# sw-4416-project-v1.net
KiCad netlist of a schematic drawn in EAGLE
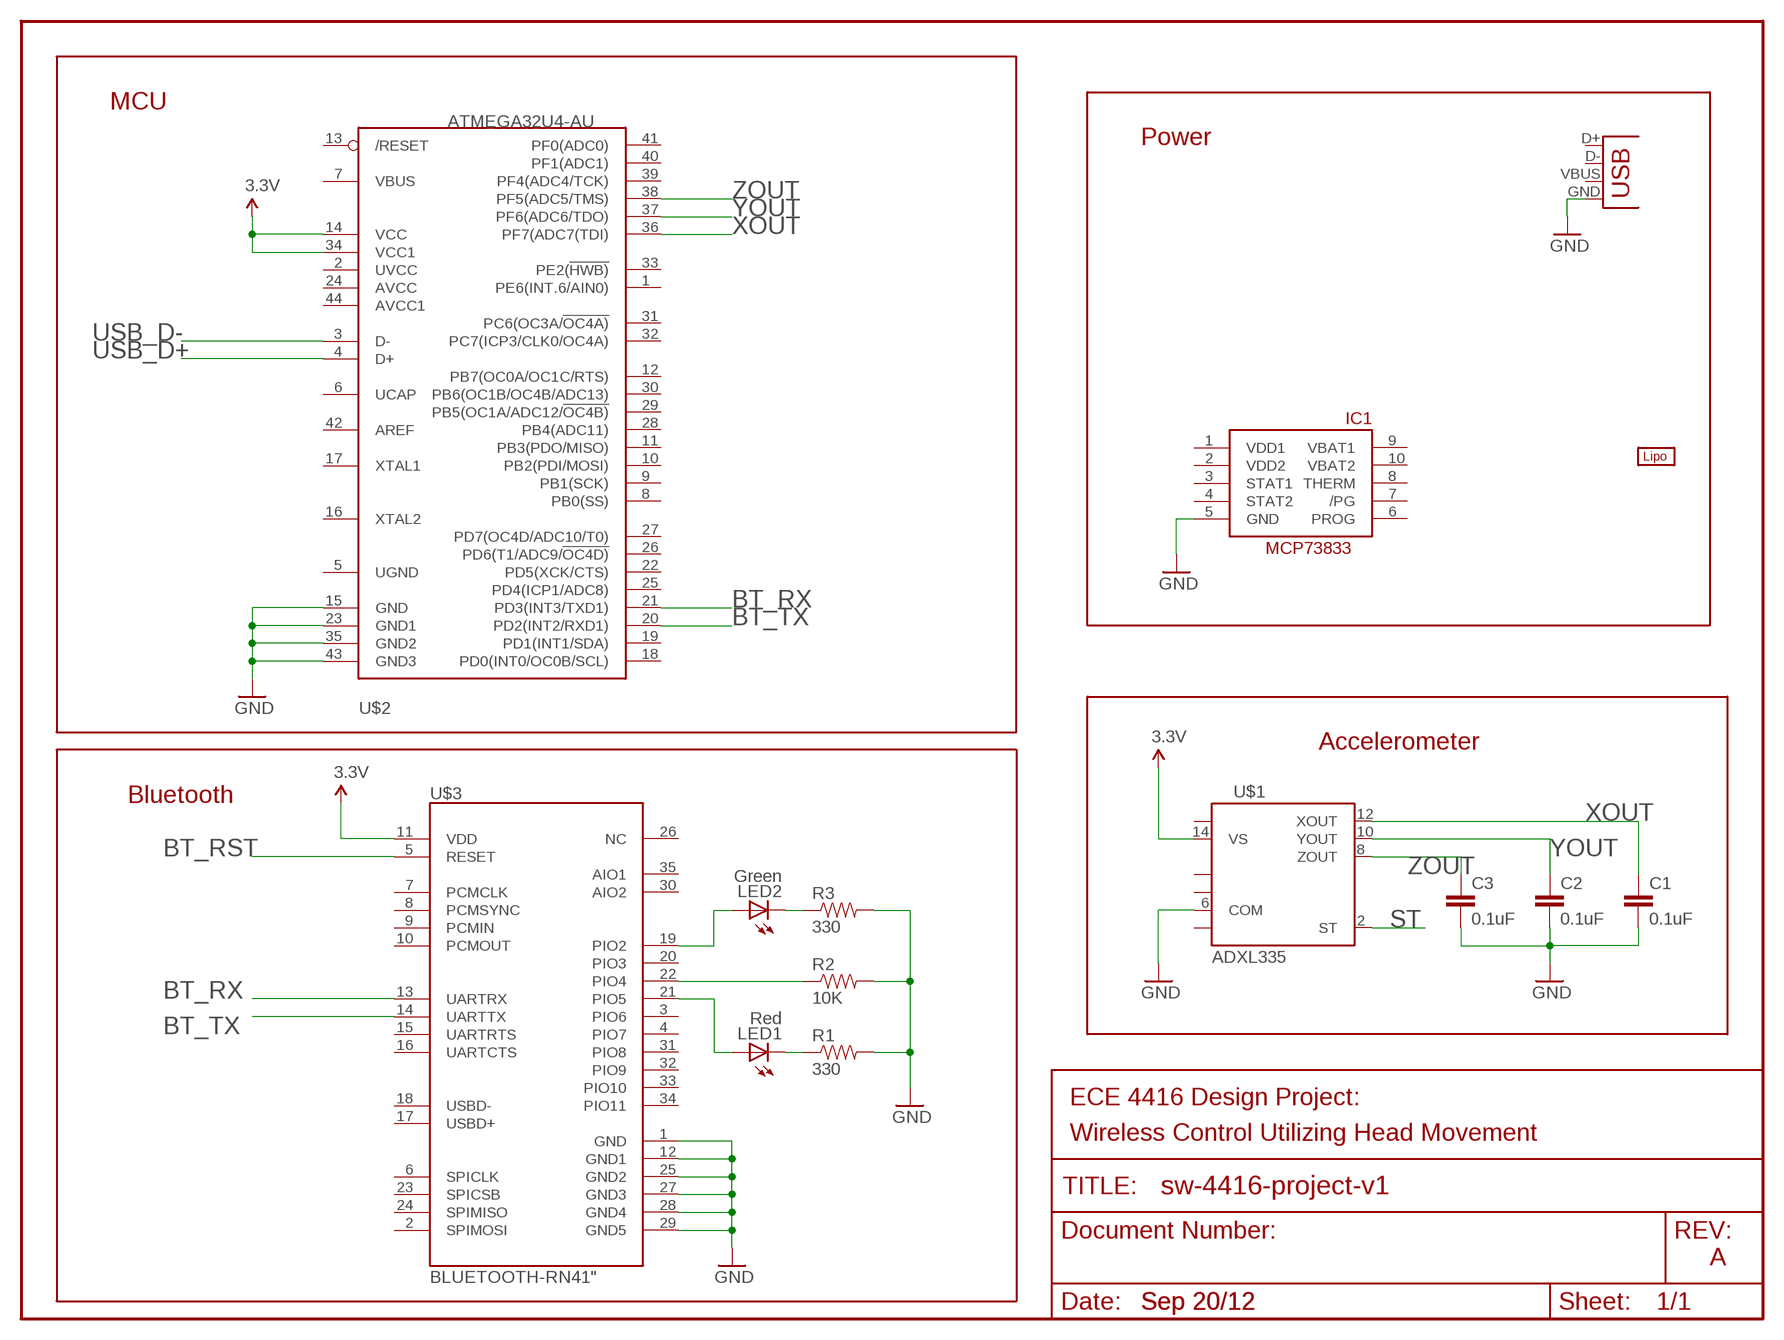
[diagram p0: schematic, sheet 1]

(export (version "E")
  (design (tool "Eeschema 10.0.6"))
  (components
    (comp (ref "C1")
      (value "0.1uF")
      (footprint "eagle-import:0603-CAP")
      (libsource (lib "eagle-import") (part "CAP0603-CAP"))
    )
    (comp (ref "C2")
      (value "0.1uF")
      (footprint "eagle-import:0603-CAP")
      (libsource (lib "eagle-import") (part "CAP0603-CAP"))
    )
    (comp (ref "C3")
      (value "0.1uF")
      (footprint "eagle-import:0603-CAP")
      (libsource (lib "eagle-import") (part "CAP0603-CAP"))
    )
    (comp (ref "IC1")
      (value "MCP73833-UN")
      (footprint "eagle-import:MSOP10")
      (libsource (lib "eagle-import") (part "MCP73833-UN"))
    )
    (comp (ref "LED1")
      (value "Red")
      (footprint "eagle-import:LED-0603")
      (libsource (lib "eagle-import") (part "LED0603"))
    )
    (comp (ref "LED2")
      (value "Green")
      (footprint "eagle-import:LED-0603")
      (libsource (lib "eagle-import") (part "LED0603"))
    )
    (comp (ref "R1")
      (value "330")
      (footprint "eagle-import:0603-RES")
      (libsource (lib "eagle-import") (part "RESISTOR0603-RES"))
    )
    (comp (ref "R2")
      (value "10K")
      (footprint "eagle-import:0603-RES")
      (libsource (lib "eagle-import") (part "RESISTOR0603-RES"))
    )
    (comp (ref "R3")
      (value "330")
      (footprint "eagle-import:0603-RES")
      (libsource (lib "eagle-import") (part "RESISTOR0603-RES"))
    )
    (comp (ref "U$1")
      (value "ADXL335")
      (footprint "eagle-import:LFCSP-16")
      (libsource (lib "eagle-import") (part "ADXL335"))
    )
    (comp (ref "U$2")
      (value "ATMEGA32U4-AU")
      (footprint "eagle-import:TQFP44")
      (libsource (lib "eagle-import") (part "ATMEGA32U4-AU"))
    )
    (comp (ref "U$3")
      (value "BLUETOOTH-RN41\"")
      (footprint "eagle-import:RN41")
      (libsource (lib "eagle-import") (part "BLUETOOTH-RN41{dblquote}"))
    )
    (comp (ref "U$4")
      (value "LIPO-OUTLINE1100")
      (footprint "eagle-import:LIPO-1100")
      (libsource (lib "eagle-import") (part "LIPO-OUTLINE1100"))
    )
    (comp (ref "X1")
      (value "USB-MICROB")
      (footprint "eagle-import:USB-MICROB")
      (libsource (lib "eagle-import") (part "USB-MICROB"))
    )
  )
  (nets
    (net (code "1") (name "/BT_RST") (class "Default")
      (node (ref "U$3") (pin "5") (pinfunction "RESET_5") (pintype "bidirectional"))
    )
    (net (code "2") (name "/BT_RX") (class "Default")
      (node (ref "U$2") (pin "21") (pinfunction "PD3(INT3/TXD1)_21") (pintype "bidirectional"))
      (node (ref "U$3") (pin "13") (pinfunction "UARTRX_13") (pintype "bidirectional"))
    )
    (net (code "3") (name "/BT_TX") (class "Default")
      (node (ref "U$2") (pin "20") (pinfunction "PD2(INT2/RXD1)_20") (pintype "bidirectional"))
      (node (ref "U$3") (pin "14") (pinfunction "UARTTX_14") (pintype "bidirectional"))
    )
    (net (code "4") (name "/ST") (class "Default")
      (node (ref "U$1") (pin "2") (pinfunction "ST_2") (pintype "bidirectional"))
    )
    (net (code "5") (name "/USB_D+") (class "Default")
      (node (ref "U$2") (pin "4") (pinfunction "D+_4") (pintype "bidirectional"))
    )
    (net (code "6") (name "/USB_D-") (class "Default")
      (node (ref "U$2") (pin "3") (pinfunction "D-_3") (pintype "bidirectional"))
    )
    (net (code "7") (name "/VDD1") (class "Default")
      (node (ref "IC1") (pin "1") (pinfunction "VDD1_1") (pintype "power_in"))
    )
    (net (code "8") (name "/VDD2") (class "Default")
      (node (ref "IC1") (pin "2") (pinfunction "VDD2_2") (pintype "power_in"))
    )
    (net (code "9") (name "/XOUT") (class "Default")
      (node (ref "C1") (pin "1") (pinfunction "1_1") (pintype "passive"))
      (node (ref "U$1") (pin "12") (pinfunction "XOUT_12") (pintype "bidirectional"))
      (node (ref "U$2") (pin "36") (pinfunction "PF7(ADC7(TDI)_36") (pintype "bidirectional"))
    )
    (net (code "10") (name "/YOUT") (class "Default")
      (node (ref "C2") (pin "1") (pinfunction "1_1") (pintype "passive"))
      (node (ref "U$1") (pin "10") (pinfunction "YOUT_10") (pintype "bidirectional"))
      (node (ref "U$2") (pin "37") (pinfunction "PF6(ADC6/TDO)_37") (pintype "bidirectional"))
    )
    (net (code "11") (name "/ZOUT") (class "Default")
      (node (ref "C3") (pin "1") (pinfunction "1_1") (pintype "passive"))
      (node (ref "U$1") (pin "8") (pinfunction "ZOUT_8") (pintype "bidirectional"))
      (node (ref "U$2") (pin "38") (pinfunction "PF5(ADC5/TMS)_38") (pintype "bidirectional"))
    )
    (net (code "12") (name "3.3V") (class "Default")
      (node (ref "U$1") (pin "14") (pinfunction "VS_14") (pintype "bidirectional"))
      (node (ref "U$2") (pin "14") (pinfunction "VCC_14") (pintype "bidirectional"))
      (node (ref "U$2") (pin "34") (pinfunction "VCC1_34") (pintype "bidirectional"))
      (node (ref "U$3") (pin "11") (pinfunction "VDD_11") (pintype "bidirectional"))
    )
    (net (code "13") (name "GND") (class "Default")
      (node (ref "C1") (pin "2") (pinfunction "2_2") (pintype "passive"))
      (node (ref "C2") (pin "2") (pinfunction "2_2") (pintype "passive"))
      (node (ref "C3") (pin "2") (pinfunction "2_2") (pintype "passive"))
      (node (ref "IC1") (pin "5") (pinfunction "GND_5") (pintype "power_in"))
      (node (ref "R1") (pin "2") (pinfunction "2_2") (pintype "passive"))
      (node (ref "R2") (pin "2") (pinfunction "2_2") (pintype "passive"))
      (node (ref "R3") (pin "2") (pinfunction "2_2") (pintype "passive"))
      (node (ref "U$1") (pin "6") (pinfunction "COM_6") (pintype "bidirectional"))
      (node (ref "U$2") (pin "15") (pinfunction "GND_15") (pintype "bidirectional"))
      (node (ref "U$2") (pin "23") (pinfunction "GND1_23") (pintype "bidirectional"))
      (node (ref "U$2") (pin "35") (pinfunction "GND2_35") (pintype "bidirectional"))
      (node (ref "U$2") (pin "43") (pinfunction "GND3_43") (pintype "bidirectional"))
      (node (ref "U$3") (pin "1") (pinfunction "GND_1") (pintype "bidirectional"))
      (node (ref "U$3") (pin "12") (pinfunction "GND1_12") (pintype "bidirectional"))
      (node (ref "U$3") (pin "25") (pinfunction "GND2_25") (pintype "bidirectional"))
      (node (ref "U$3") (pin "27") (pinfunction "GND3_27") (pintype "bidirectional"))
      (node (ref "U$3") (pin "28") (pinfunction "GND4_28") (pintype "bidirectional"))
      (node (ref "U$3") (pin "29") (pinfunction "GND5_29") (pintype "bidirectional"))
      (node (ref "X1") (pin "GND") (pinfunction "GND_GND") (pintype "bidirectional"))
    )
    (net (code "14") (name "Net-(LED1-PadC)") (class "Default")
      (node (ref "LED1") (pin "C") (pinfunction "C_C") (pintype "passive"))
      (node (ref "R1") (pin "1") (pinfunction "1_1") (pintype "passive"))
    )
    (net (code "15") (name "Net-(LED2-PadC)") (class "Default")
      (node (ref "LED2") (pin "C") (pinfunction "C_C") (pintype "passive"))
      (node (ref "R3") (pin "1") (pinfunction "1_1") (pintype "passive"))
    )
    (net (code "16") (name "Net-(U$3-PIO2)") (class "Default")
      (node (ref "LED2") (pin "A") (pinfunction "A_A") (pintype "passive"))
      (node (ref "U$3") (pin "19") (pinfunction "PIO2_19") (pintype "bidirectional"))
    )
    (net (code "17") (name "Net-(U$3-PIO4)") (class "Default")
      (node (ref "R2") (pin "1") (pinfunction "1_1") (pintype "passive"))
      (node (ref "U$3") (pin "22") (pinfunction "PIO4_22") (pintype "bidirectional"))
    )
    (net (code "18") (name "Net-(U$3-PIO5)") (class "Default")
      (node (ref "LED1") (pin "A") (pinfunction "A_A") (pintype "passive"))
      (node (ref "U$3") (pin "21") (pinfunction "PIO5_21") (pintype "bidirectional"))
    )
    (net (code "19") (name "unconnected-(IC1-PROG-Pad6)") (class "Default")
      (node (ref "IC1") (pin "6") (pinfunction "PROG_6") (pintype "input"))
    )
    (net (code "20") (name "unconnected-(IC1-STAT1-Pad3)") (class "Default")
      (node (ref "IC1") (pin "3") (pinfunction "STAT1_3") (pintype "passive"))
    )
    (net (code "21") (name "unconnected-(IC1-STAT2-Pad4)") (class "Default")
      (node (ref "IC1") (pin "4") (pinfunction "STAT2_4") (pintype "passive"))
    )
    (net (code "22") (name "unconnected-(IC1-THERM-Pad8)") (class "Default")
      (node (ref "IC1") (pin "8") (pinfunction "THERM_8") (pintype "bidirectional"))
    )
    (net (code "23") (name "unconnected-(IC1-VBAT1-Pad9)") (class "Default")
      (node (ref "IC1") (pin "9") (pinfunction "VBAT1_9") (pintype "output"))
    )
    (net (code "24") (name "unconnected-(IC1-VBAT2-Pad10)") (class "Default")
      (node (ref "IC1") (pin "10") (pinfunction "VBAT2_10") (pintype "output"))
    )
    (net (code "25") (name "unconnected-(IC1-{slash}PG-Pad7)") (class "Default")
      (node (ref "IC1") (pin "7") (pinfunction "/PG_7") (pintype "passive"))
    )
    (net (code "26") (name "unconnected-(U$1-COM-Pad3)") (class "Default")
      (node (ref "U$1") (pin "3") (pinfunction "COM_3") (pintype "bidirectional"))
    )
    (net (code "27") (name "unconnected-(U$1-COM-Pad5)") (class "Default")
      (node (ref "U$1") (pin "5") (pinfunction "COM_5") (pintype "bidirectional"))
    )
    (net (code "28") (name "unconnected-(U$1-COM-Pad7)") (class "Default")
      (node (ref "U$1") (pin "7") (pinfunction "COM_7") (pintype "bidirectional"))
    )
    (net (code "29") (name "unconnected-(U$1-VS-Pad15)") (class "Default")
      (node (ref "U$1") (pin "15") (pinfunction "VS_15") (pintype "bidirectional"))
    )
    (net (code "30") (name "unconnected-(U$2-AREF-Pad42)") (class "Default")
      (node (ref "U$2") (pin "42") (pinfunction "AREF_42") (pintype "bidirectional"))
    )
    (net (code "31") (name "unconnected-(U$2-AVCC-Pad24)") (class "Default")
      (node (ref "U$2") (pin "24") (pinfunction "AVCC_24") (pintype "bidirectional"))
    )
    (net (code "32") (name "unconnected-(U$2-AVCC1-Pad44)") (class "Default")
      (node (ref "U$2") (pin "44") (pinfunction "AVCC1_44") (pintype "bidirectional"))
    )
    (net (code "33") (name "unconnected-(U$2-PB0(SS)-Pad8)") (class "Default")
      (node (ref "U$2") (pin "8") (pinfunction "PB0(SS)_8") (pintype "bidirectional"))
    )
    (net (code "34") (name "unconnected-(U$2-PB1(SCK)-Pad9)") (class "Default")
      (node (ref "U$2") (pin "9") (pinfunction "PB1(SCK)_9") (pintype "bidirectional"))
    )
    (net (code "35") (name "unconnected-(U$2-PB2(PDI{slash}MOSI)-Pad10)") (class "Default")
      (node (ref "U$2") (pin "10") (pinfunction "PB2(PDI/MOSI)_10") (pintype "bidirectional"))
    )
    (net (code "36") (name "unconnected-(U$2-PB3(PDO{slash}MISO)-Pad11)") (class "Default")
      (node (ref "U$2") (pin "11") (pinfunction "PB3(PDO/MISO)_11") (pintype "bidirectional"))
    )
    (net (code "37") (name "unconnected-(U$2-PB4(ADC11)-Pad28)") (class "Default")
      (node (ref "U$2") (pin "28") (pinfunction "PB4(ADC11)_28") (pintype "bidirectional"))
    )
    (net (code "38") (name "unconnected-(U$2-PB5(OC1A{slash}ADC12{slash}~{OC4B})-Pad29)") (class "Default")
      (node (ref "U$2") (pin "29") (pinfunction "PB5(OC1A/ADC12/~{OC4B})_29") (pintype "bidirectional"))
    )
    (net (code "39") (name "unconnected-(U$2-PB6(OC1B{slash}OC4B{slash}ADC13)-Pad30)") (class "Default")
      (node (ref "U$2") (pin "30") (pinfunction "PB6(OC1B/OC4B/ADC13)_30") (pintype "bidirectional"))
    )
    (net (code "40") (name "unconnected-(U$2-PB7(OC0A{slash}OC1C{slash}RTS)-Pad12)") (class "Default")
      (node (ref "U$2") (pin "12") (pinfunction "PB7(OC0A/OC1C/RTS)_12") (pintype "bidirectional"))
    )
    (net (code "41") (name "unconnected-(U$2-PC6(OC3A{slash}~{OC4A})-Pad31)") (class "Default")
      (node (ref "U$2") (pin "31") (pinfunction "PC6(OC3A/~{OC4A})_31") (pintype "bidirectional"))
    )
    (net (code "42") (name "unconnected-(U$2-PC7(ICP3{slash}CLK0{slash}OC4A)-Pad32)") (class "Default")
      (node (ref "U$2") (pin "32") (pinfunction "PC7(ICP3/CLK0/OC4A)_32") (pintype "bidirectional"))
    )
    (net (code "43") (name "unconnected-(U$2-PD0(INT0{slash}OC0B{slash}SCL)-Pad18)") (class "Default")
      (node (ref "U$2") (pin "18") (pinfunction "PD0(INT0/OC0B/SCL)_18") (pintype "bidirectional"))
    )
    (net (code "44") (name "unconnected-(U$2-PD1(INT1{slash}SDA)-Pad19)") (class "Default")
      (node (ref "U$2") (pin "19") (pinfunction "PD1(INT1/SDA)_19") (pintype "bidirectional"))
    )
    (net (code "45") (name "unconnected-(U$2-PD4(ICP1{slash}ADC8)-Pad25)") (class "Default")
      (node (ref "U$2") (pin "25") (pinfunction "PD4(ICP1/ADC8)_25") (pintype "bidirectional"))
    )
    (net (code "46") (name "unconnected-(U$2-PD5(XCK{slash}CTS)-Pad22)") (class "Default")
      (node (ref "U$2") (pin "22") (pinfunction "PD5(XCK/CTS)_22") (pintype "bidirectional"))
    )
    (net (code "47") (name "unconnected-(U$2-PD6(T1{slash}ADC9{slash}~{OC4D})-Pad26)") (class "Default")
      (node (ref "U$2") (pin "26") (pinfunction "PD6(T1/ADC9/~{OC4D})_26") (pintype "bidirectional"))
    )
    (net (code "48") (name "unconnected-(U$2-PD7(OC4D{slash}ADC10{slash}T0)-Pad27)") (class "Default")
      (node (ref "U$2") (pin "27") (pinfunction "PD7(OC4D/ADC10/T0)_27") (pintype "bidirectional"))
    )
    (net (code "49") (name "unconnected-(U$2-PE2(~{HWB})-Pad33)") (class "Default")
      (node (ref "U$2") (pin "33") (pinfunction "PE2(~{HWB})_33") (pintype "bidirectional"))
    )
    (net (code "50") (name "unconnected-(U$2-PE6(INT.6{slash}AIN0)-Pad1)") (class "Default")
      (node (ref "U$2") (pin "1") (pinfunction "PE6(INT.6/AIN0)_1") (pintype "bidirectional"))
    )
    (net (code "51") (name "unconnected-(U$2-PF0(ADC0)-Pad41)") (class "Default")
      (node (ref "U$2") (pin "41") (pinfunction "PF0(ADC0)_41") (pintype "bidirectional"))
    )
    (net (code "52") (name "unconnected-(U$2-PF1(ADC1)-Pad40)") (class "Default")
      (node (ref "U$2") (pin "40") (pinfunction "PF1(ADC1)_40") (pintype "bidirectional"))
    )
    (net (code "53") (name "unconnected-(U$2-PF4(ADC4{slash}TCK)-Pad39)") (class "Default")
      (node (ref "U$2") (pin "39") (pinfunction "PF4(ADC4/TCK)_39") (pintype "bidirectional"))
    )
    (net (code "54") (name "unconnected-(U$2-UCAP-Pad6)") (class "Default")
      (node (ref "U$2") (pin "6") (pinfunction "UCAP_6") (pintype "bidirectional"))
    )
    (net (code "55") (name "unconnected-(U$2-UGND-Pad5)") (class "Default")
      (node (ref "U$2") (pin "5") (pinfunction "UGND_5") (pintype "bidirectional"))
    )
    (net (code "56") (name "unconnected-(U$2-UVCC-Pad2)") (class "Default")
      (node (ref "U$2") (pin "2") (pinfunction "UVCC_2") (pintype "bidirectional"))
    )
    (net (code "57") (name "unconnected-(U$2-VBUS-Pad7)") (class "Default")
      (node (ref "U$2") (pin "7") (pinfunction "VBUS_7") (pintype "bidirectional"))
    )
    (net (code "58") (name "unconnected-(U$2-XTAL1-Pad17)") (class "Default")
      (node (ref "U$2") (pin "17") (pinfunction "XTAL1_17") (pintype "bidirectional"))
    )
    (net (code "59") (name "unconnected-(U$2-XTAL2-Pad16)") (class "Default")
      (node (ref "U$2") (pin "16") (pinfunction "XTAL2_16") (pintype "bidirectional"))
    )
    (net (code "60") (name "unconnected-(U$2-{slash}RESET-Pad13)") (class "Default")
      (node (ref "U$2") (pin "13") (pinfunction "/RESET_13") (pintype "bidirectional"))
    )
    (net (code "61") (name "unconnected-(U$3-AIO1-Pad35)") (class "Default")
      (node (ref "U$3") (pin "35") (pinfunction "AIO1_35") (pintype "bidirectional"))
    )
    (net (code "62") (name "unconnected-(U$3-AIO2-Pad30)") (class "Default")
      (node (ref "U$3") (pin "30") (pinfunction "AIO2_30") (pintype "bidirectional"))
    )
    (net (code "63") (name "unconnected-(U$3-NC-Pad26)") (class "Default")
      (node (ref "U$3") (pin "26") (pinfunction "NC_26") (pintype "bidirectional"))
    )
    (net (code "64") (name "unconnected-(U$3-PCMCLK-Pad7)") (class "Default")
      (node (ref "U$3") (pin "7") (pinfunction "PCMCLK_7") (pintype "bidirectional"))
    )
    (net (code "65") (name "unconnected-(U$3-PCMIN-Pad9)") (class "Default")
      (node (ref "U$3") (pin "9") (pinfunction "PCMIN_9") (pintype "bidirectional"))
    )
    (net (code "66") (name "unconnected-(U$3-PCMOUT-Pad10)") (class "Default")
      (node (ref "U$3") (pin "10") (pinfunction "PCMOUT_10") (pintype "bidirectional"))
    )
    (net (code "67") (name "unconnected-(U$3-PCMSYNC-Pad8)") (class "Default")
      (node (ref "U$3") (pin "8") (pinfunction "PCMSYNC_8") (pintype "bidirectional"))
    )
    (net (code "68") (name "unconnected-(U$3-PIO3-Pad20)") (class "Default")
      (node (ref "U$3") (pin "20") (pinfunction "PIO3_20") (pintype "bidirectional"))
    )
    (net (code "69") (name "unconnected-(U$3-PIO6-Pad3)") (class "Default")
      (node (ref "U$3") (pin "3") (pinfunction "PIO6_3") (pintype "bidirectional"))
    )
    (net (code "70") (name "unconnected-(U$3-PIO7-Pad4)") (class "Default")
      (node (ref "U$3") (pin "4") (pinfunction "PIO7_4") (pintype "bidirectional"))
    )
    (net (code "71") (name "unconnected-(U$3-PIO8-Pad31)") (class "Default")
      (node (ref "U$3") (pin "31") (pinfunction "PIO8_31") (pintype "bidirectional"))
    )
    (net (code "72") (name "unconnected-(U$3-PIO9-Pad32)") (class "Default")
      (node (ref "U$3") (pin "32") (pinfunction "PIO9_32") (pintype "bidirectional"))
    )
    (net (code "73") (name "unconnected-(U$3-PIO10-Pad33)") (class "Default")
      (node (ref "U$3") (pin "33") (pinfunction "PIO10_33") (pintype "bidirectional"))
    )
    (net (code "74") (name "unconnected-(U$3-PIO11-Pad34)") (class "Default")
      (node (ref "U$3") (pin "34") (pinfunction "PIO11_34") (pintype "bidirectional"))
    )
    (net (code "75") (name "unconnected-(U$3-SPICLK-Pad6)") (class "Default")
      (node (ref "U$3") (pin "6") (pinfunction "SPICLK_6") (pintype "bidirectional"))
    )
    (net (code "76") (name "unconnected-(U$3-SPICSB-Pad23)") (class "Default")
      (node (ref "U$3") (pin "23") (pinfunction "SPICSB_23") (pintype "bidirectional"))
    )
    (net (code "77") (name "unconnected-(U$3-SPIMISO-Pad24)") (class "Default")
      (node (ref "U$3") (pin "24") (pinfunction "SPIMISO_24") (pintype "bidirectional"))
    )
    (net (code "78") (name "unconnected-(U$3-SPIMOSI-Pad2)") (class "Default")
      (node (ref "U$3") (pin "2") (pinfunction "SPIMOSI_2") (pintype "bidirectional"))
    )
    (net (code "79") (name "unconnected-(U$3-UARTCTS-Pad16)") (class "Default")
      (node (ref "U$3") (pin "16") (pinfunction "UARTCTS_16") (pintype "bidirectional"))
    )
    (net (code "80") (name "unconnected-(U$3-UARTRTS-Pad15)") (class "Default")
      (node (ref "U$3") (pin "15") (pinfunction "UARTRTS_15") (pintype "bidirectional"))
    )
    (net (code "81") (name "unconnected-(U$3-USBD+-Pad17)") (class "Default")
      (node (ref "U$3") (pin "17") (pinfunction "USBD+_17") (pintype "bidirectional"))
    )
    (net (code "82") (name "unconnected-(U$3-USBD--Pad18)") (class "Default")
      (node (ref "U$3") (pin "18") (pinfunction "USBD-_18") (pintype "bidirectional"))
    )
    (net (code "83") (name "unconnected-(X1-PadD+)") (class "Default")
      (node (ref "X1") (pin "D+") (pinfunction "D+_D+") (pintype "bidirectional"))
    )
    (net (code "84") (name "unconnected-(X1-PadD-)") (class "Default")
      (node (ref "X1") (pin "D-") (pinfunction "D-_D-") (pintype "bidirectional"))
    )
    (net (code "85") (name "unconnected-(X1-PadVBUS)") (class "Default")
      (node (ref "X1") (pin "VBUS") (pinfunction "VBUS_VBUS") (pintype "bidirectional"))
    )
  )
)
